# Configurable_RC_Filter.net
KiCad netlist of a schematic drawn in EAGLE
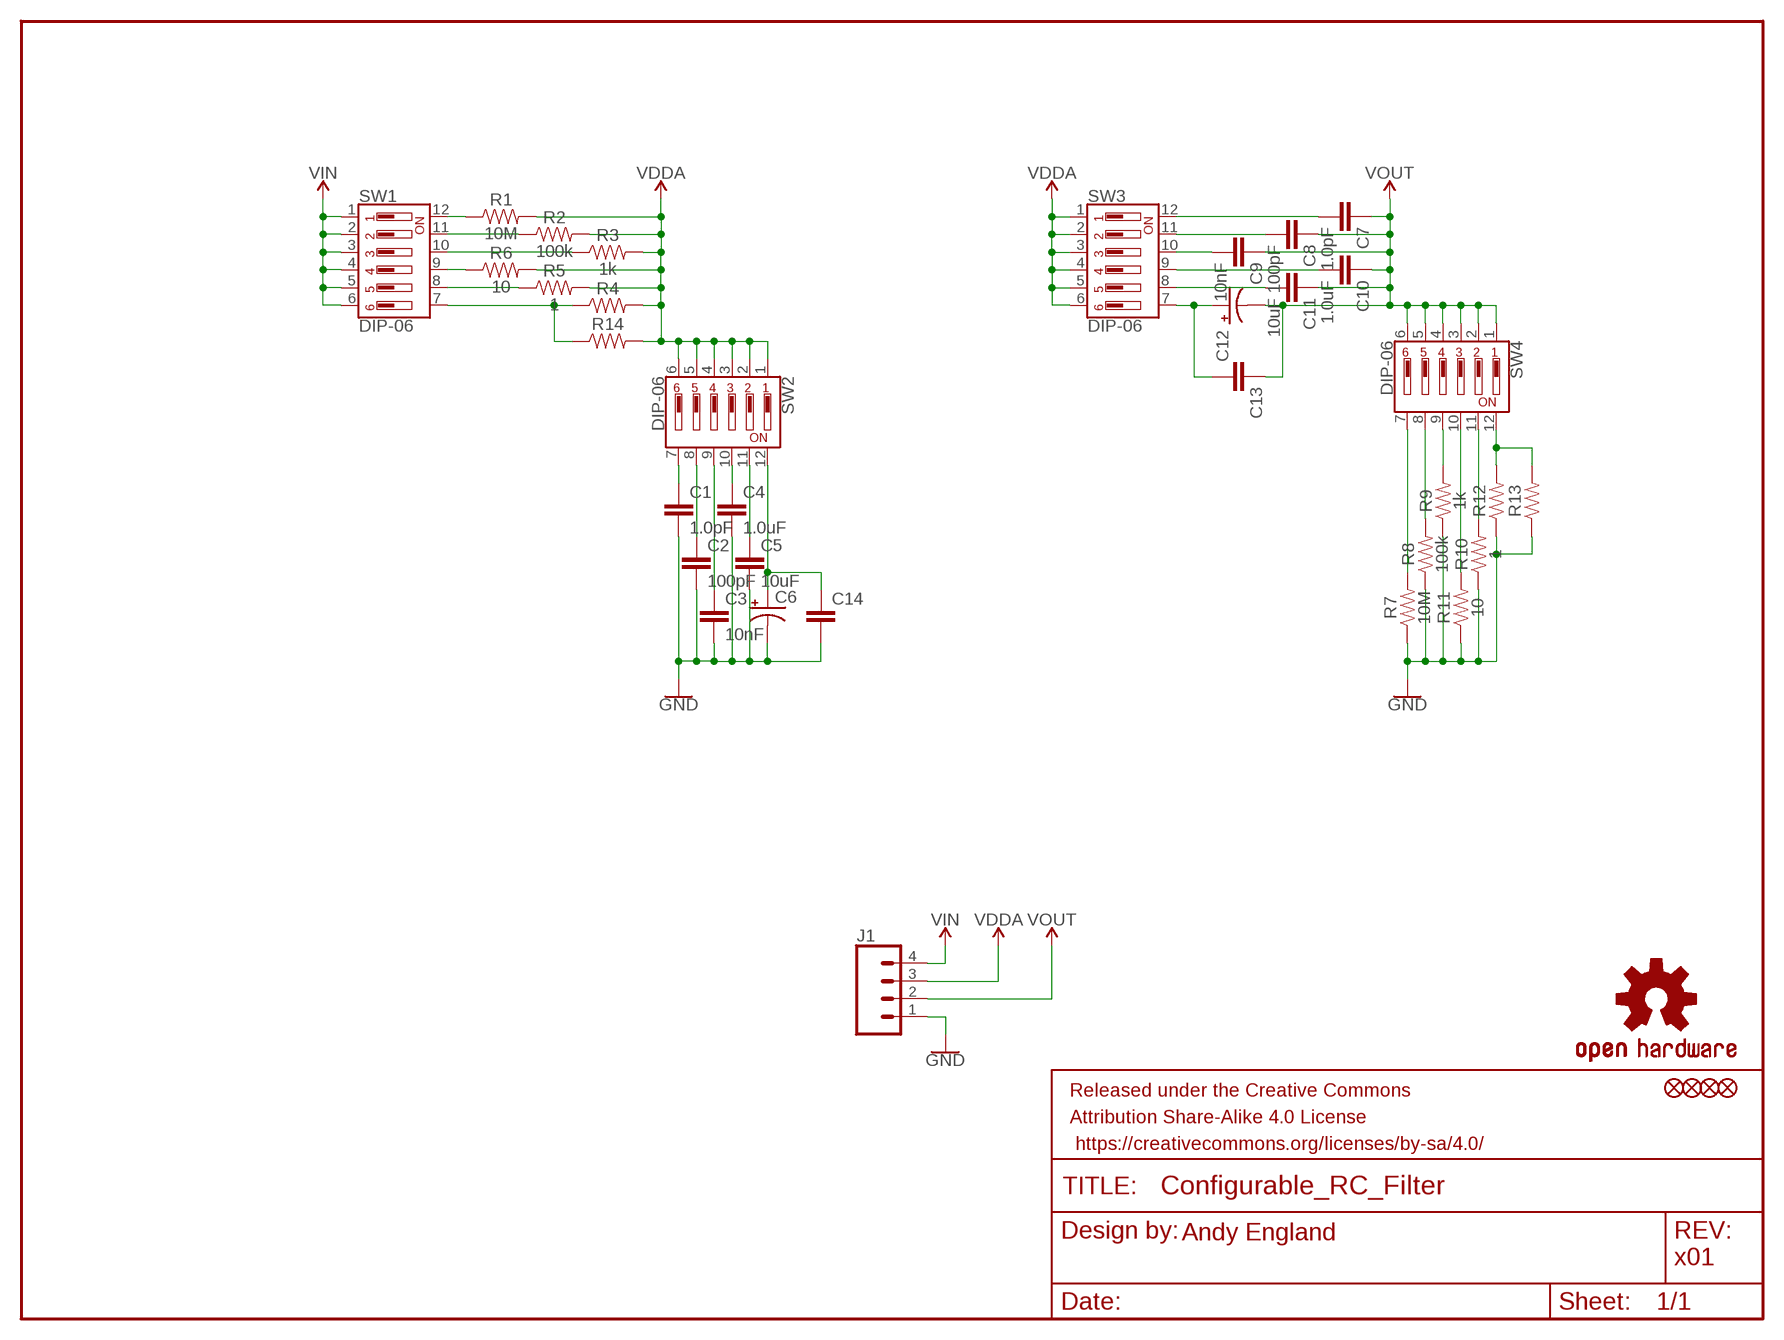
[diagram p0: schematic, sheet 1]

(export (version "E")
  (design (tool "Eeschema 10.0.6"))
  (components
    (comp (ref "C1")
      (value "1.0pF")
      (footprint "eagle-import:0603")
      (libsource (lib "eagle-import") (part "1.0PF-0603-50V-25%"))
    )
    (comp (ref "C2")
      (value "100pF")
      (footprint "eagle-import:0603")
      (libsource (lib "eagle-import") (part "100PF-0603-50V-5%"))
    )
    (comp (ref "C3")
      (value "10nF")
      (footprint "eagle-import:0603")
      (libsource (lib "eagle-import") (part "10NF-0603-50V-10%"))
    )
    (comp (ref "C4")
      (value "1.0uF")
      (footprint "eagle-import:0603")
      (libsource (lib "eagle-import") (part "1.0UF-0603-16V-10%"))
    )
    (comp (ref "C5")
      (value "10uF")
      (footprint "eagle-import:0603")
      (libsource (lib "eagle-import") (part "10UF-0603-6.3V-20%"))
    )
    (comp (ref "C6")
      (value "1000UF-RADIAL-5MM-25V-20%-NO-SILK")
      (footprint "eagle-import:CPOL-RADIAL-5MM-10MM-NS")
      (libsource (lib "eagle-import") (part "1000UF-RADIAL-5MM-25V-20%-NO-SILK"))
    )
    (comp (ref "C7")
      (value "1.0pF")
      (footprint "eagle-import:0603")
      (libsource (lib "eagle-import") (part "1.0PF-0603-50V-25%"))
    )
    (comp (ref "C8")
      (value "100pF")
      (footprint "eagle-import:0603")
      (libsource (lib "eagle-import") (part "100PF-0603-50V-5%"))
    )
    (comp (ref "C9")
      (value "10nF")
      (footprint "eagle-import:0603")
      (libsource (lib "eagle-import") (part "10NF-0603-50V-10%"))
    )
    (comp (ref "C10")
      (value "1.0uF")
      (footprint "eagle-import:0603")
      (libsource (lib "eagle-import") (part "1.0UF-0603-16V-10%"))
    )
    (comp (ref "C11")
      (value "10uF")
      (footprint "eagle-import:0603")
      (libsource (lib "eagle-import") (part "10UF-0603-6.3V-20%"))
    )
    (comp (ref "C12")
      (value "1000UF-RADIAL-5MM-25V-20%-NO-SILK")
      (footprint "eagle-import:CPOL-RADIAL-5MM-10MM-NS")
      (libsource (lib "eagle-import") (part "1000UF-RADIAL-5MM-25V-20%-NO-SILK"))
    )
    (comp (ref "C13")
      (value "CAP-0603")
      (footprint "eagle-import:0603")
      (libsource (lib "eagle-import") (part "CAP-0603"))
    )
    (comp (ref "C14")
      (value "CAP-0603")
      (footprint "eagle-import:0603")
      (libsource (lib "eagle-import") (part "CAP-0603"))
    )
    (comp (ref "FD1")
      (value "FIDUCIAL1X2")
      (footprint "eagle-import:FIDUCIAL-1X2")
      (libsource (lib "eagle-import") (part "FIDUCIAL1X2"))
    )
    (comp (ref "FD2")
      (value "FIDUCIAL1X2")
      (footprint "eagle-import:FIDUCIAL-1X2")
      (libsource (lib "eagle-import") (part "FIDUCIAL1X2"))
    )
    (comp (ref "FD3")
      (value "FIDUCIAL1X2")
      (footprint "eagle-import:FIDUCIAL-1X2")
      (libsource (lib "eagle-import") (part "FIDUCIAL1X2"))
    )
    (comp (ref "FD4")
      (value "FIDUCIAL1X2")
      (footprint "eagle-import:FIDUCIAL-1X2")
      (libsource (lib "eagle-import") (part "FIDUCIAL1X2"))
    )
    (comp (ref "FRAME1")
      (value "FRAME-LETTER")
      (footprint "eagle-import:CREATIVE_COMMONS")
      (libsource (lib "eagle-import") (part "FRAME-LETTER"))
    )
    (comp (ref "J1")
      (value "CONN_041X04_NO_SILK")
      (footprint "eagle-import:1X04_NO_SILK")
      (libsource (lib "eagle-import") (part "CONN_041X04_NO_SILK"))
    )
    (comp (ref "LOGO1")
      (value "OSHW-LOGOS")
      (footprint "eagle-import:OSHW-LOGO-S")
      (libsource (lib "eagle-import") (part "OSHW-LOGOS"))
    )
    (comp (ref "R1")
      (value "10M")
      (footprint "eagle-import:0603")
      (libsource (lib "eagle-import") (part "10MOHM-0603-1/10W-5%"))
    )
    (comp (ref "R2")
      (value "100k")
      (footprint "eagle-import:0603")
      (libsource (lib "eagle-import") (part "100KOHM-0603-1/10W-1%"))
    )
    (comp (ref "R3")
      (value "1k")
      (footprint "eagle-import:0603")
      (libsource (lib "eagle-import") (part "1KOHM-0603-1/10W-1%"))
    )
    (comp (ref "R4")
      (value "RESISTORAXIAL-0.3")
      (footprint "eagle-import:AXIAL-0.3")
      (libsource (lib "eagle-import") (part "RESISTORAXIAL-0.3"))
    )
    (comp (ref "R5")
      (value "1")
      (footprint "eagle-import:0603")
      (libsource (lib "eagle-import") (part "1OHM-0603-1/10W-1%"))
    )
    (comp (ref "R6")
      (value "10")
      (footprint "eagle-import:0603")
      (libsource (lib "eagle-import") (part "10OHM-0603-1/10W-1%"))
    )
    (comp (ref "R7")
      (value "10M")
      (footprint "eagle-import:0603")
      (libsource (lib "eagle-import") (part "10MOHM-0603-1/10W-5%"))
    )
    (comp (ref "R8")
      (value "100k")
      (footprint "eagle-import:0603")
      (libsource (lib "eagle-import") (part "100KOHM-0603-1/10W-1%"))
    )
    (comp (ref "R9")
      (value "1k")
      (footprint "eagle-import:0603")
      (libsource (lib "eagle-import") (part "1KOHM-0603-1/10W-1%"))
    )
    (comp (ref "R10")
      (value "1")
      (footprint "eagle-import:0603")
      (libsource (lib "eagle-import") (part "1OHM-0603-1/10W-1%"))
    )
    (comp (ref "R11")
      (value "10")
      (footprint "eagle-import:0603")
      (libsource (lib "eagle-import") (part "10OHM-0603-1/10W-1%"))
    )
    (comp (ref "R12")
      (value "RESISTORAXIAL-0.3")
      (footprint "eagle-import:AXIAL-0.3")
      (libsource (lib "eagle-import") (part "RESISTORAXIAL-0.3"))
    )
    (comp (ref "R13")
      (value "RESISTOR0603")
      (footprint "eagle-import:0603")
      (libsource (lib "eagle-import") (part "RESISTOR0603"))
    )
    (comp (ref "R14")
      (value "RESISTOR0603")
      (footprint "eagle-import:0603")
      (libsource (lib "eagle-import") (part "RESISTOR0603"))
    )
    (comp (ref "SW1")
      (value "DIP-06")
      (footprint "eagle-import:DIPSWITCH-06-SMD")
      (libsource (lib "eagle-import") (part "DIP-06"))
    )
    (comp (ref "SW2")
      (value "DIP-06")
      (footprint "eagle-import:DIPSWITCH-06-SMD")
      (libsource (lib "eagle-import") (part "DIP-06"))
    )
    (comp (ref "SW3")
      (value "DIP-06")
      (footprint "eagle-import:DIPSWITCH-06-SMD")
      (libsource (lib "eagle-import") (part "DIP-06"))
    )
    (comp (ref "SW4")
      (value "DIP-06")
      (footprint "eagle-import:DIPSWITCH-06-SMD")
      (libsource (lib "eagle-import") (part "DIP-06"))
    )
  )
  (nets
    (net (code "1") (name "GND") (class "Default")
      (node (ref "C1") (pin "2") (pinfunction "2_2") (pintype "passive"))
      (node (ref "C14") (pin "2") (pinfunction "2_2") (pintype "passive"))
      (node (ref "C2") (pin "2") (pinfunction "2_2") (pintype "passive"))
      (node (ref "C3") (pin "2") (pinfunction "2_2") (pintype "passive"))
      (node (ref "C4") (pin "2") (pinfunction "2_2") (pintype "passive"))
      (node (ref "C5") (pin "2") (pinfunction "2_2") (pintype "passive"))
      (node (ref "C6") (pin "-") (pinfunction "-_-") (pintype "passive"))
      (node (ref "J1") (pin "1") (pinfunction "1_1") (pintype "passive"))
      (node (ref "R10") (pin "1") (pinfunction "1_1") (pintype "passive"))
      (node (ref "R11") (pin "1") (pinfunction "1_1") (pintype "passive"))
      (node (ref "R12") (pin "P$1") (pinfunction "1_P$1") (pintype "passive"))
      (node (ref "R13") (pin "1") (pinfunction "1_1") (pintype "passive"))
      (node (ref "R7") (pin "1") (pinfunction "1_1") (pintype "passive"))
      (node (ref "R8") (pin "1") (pinfunction "1_1") (pintype "passive"))
      (node (ref "R9") (pin "1") (pinfunction "1_1") (pintype "passive"))
    )
    (net (code "2") (name "Net-(C1-Pad1)") (class "Default")
      (node (ref "C1") (pin "1") (pinfunction "1_1") (pintype "passive"))
      (node (ref "SW2") (pin "7") (pinfunction "7_7") (pintype "bidirectional"))
    )
    (net (code "3") (name "Net-(C2-Pad1)") (class "Default")
      (node (ref "C2") (pin "1") (pinfunction "1_1") (pintype "passive"))
      (node (ref "SW2") (pin "8") (pinfunction "8_8") (pintype "bidirectional"))
    )
    (net (code "4") (name "Net-(C3-Pad1)") (class "Default")
      (node (ref "C3") (pin "1") (pinfunction "1_1") (pintype "passive"))
      (node (ref "SW2") (pin "9") (pinfunction "9_9") (pintype "bidirectional"))
    )
    (net (code "5") (name "Net-(C4-Pad1)") (class "Default")
      (node (ref "C4") (pin "1") (pinfunction "1_1") (pintype "passive"))
      (node (ref "SW2") (pin "10") (pinfunction "10_10") (pintype "bidirectional"))
    )
    (net (code "6") (name "Net-(C5-Pad1)") (class "Default")
      (node (ref "C5") (pin "1") (pinfunction "1_1") (pintype "passive"))
      (node (ref "SW2") (pin "11") (pinfunction "11_11") (pintype "bidirectional"))
    )
    (net (code "7") (name "Net-(C7-Pad2)") (class "Default")
      (node (ref "C7") (pin "2") (pinfunction "2_2") (pintype "passive"))
      (node (ref "SW3") (pin "12") (pinfunction "12_12") (pintype "bidirectional"))
    )
    (net (code "8") (name "Net-(C8-Pad2)") (class "Default")
      (node (ref "C8") (pin "2") (pinfunction "2_2") (pintype "passive"))
      (node (ref "SW3") (pin "11") (pinfunction "11_11") (pintype "bidirectional"))
    )
    (net (code "9") (name "Net-(C9-Pad2)") (class "Default")
      (node (ref "C9") (pin "2") (pinfunction "2_2") (pintype "passive"))
      (node (ref "SW3") (pin "10") (pinfunction "10_10") (pintype "bidirectional"))
    )
    (net (code "10") (name "Net-(C10-Pad2)") (class "Default")
      (node (ref "C10") (pin "2") (pinfunction "2_2") (pintype "passive"))
      (node (ref "SW3") (pin "9") (pinfunction "9_9") (pintype "bidirectional"))
    )
    (net (code "11") (name "Net-(C11-Pad2)") (class "Default")
      (node (ref "C11") (pin "2") (pinfunction "2_2") (pintype "passive"))
      (node (ref "SW3") (pin "8") (pinfunction "8_8") (pintype "bidirectional"))
    )
    (net (code "12") (name "Net-(C12-Pad+)") (class "Default")
      (node (ref "C12") (pin "+") (pinfunction "+_+") (pintype "passive"))
      (node (ref "C13") (pin "2") (pinfunction "2_2") (pintype "passive"))
      (node (ref "SW3") (pin "7") (pinfunction "7_7") (pintype "bidirectional"))
    )
    (net (code "13") (name "Net-(C14-Pad1)") (class "Default")
      (node (ref "C14") (pin "1") (pinfunction "1_1") (pintype "passive"))
      (node (ref "C6") (pin "+") (pinfunction "+_+") (pintype "passive"))
      (node (ref "SW2") (pin "12") (pinfunction "12_12") (pintype "bidirectional"))
    )
    (net (code "14") (name "Net-(R1-Pad1)") (class "Default")
      (node (ref "R1") (pin "1") (pinfunction "1_1") (pintype "passive"))
      (node (ref "SW1") (pin "12") (pinfunction "12_12") (pintype "bidirectional"))
    )
    (net (code "15") (name "Net-(R2-Pad1)") (class "Default")
      (node (ref "R2") (pin "1") (pinfunction "1_1") (pintype "passive"))
      (node (ref "SW1") (pin "11") (pinfunction "11_11") (pintype "bidirectional"))
    )
    (net (code "16") (name "Net-(R3-Pad1)") (class "Default")
      (node (ref "R3") (pin "1") (pinfunction "1_1") (pintype "passive"))
      (node (ref "SW1") (pin "10") (pinfunction "10_10") (pintype "bidirectional"))
    )
    (net (code "17") (name "Net-(R4-1)") (class "Default")
      (node (ref "R14") (pin "1") (pinfunction "1_1") (pintype "passive"))
      (node (ref "R4") (pin "P$1") (pinfunction "1_P$1") (pintype "passive"))
      (node (ref "SW1") (pin "7") (pinfunction "7_7") (pintype "bidirectional"))
    )
    (net (code "18") (name "Net-(R5-Pad1)") (class "Default")
      (node (ref "R5") (pin "1") (pinfunction "1_1") (pintype "passive"))
      (node (ref "SW1") (pin "8") (pinfunction "8_8") (pintype "bidirectional"))
    )
    (net (code "19") (name "Net-(R6-Pad1)") (class "Default")
      (node (ref "R6") (pin "1") (pinfunction "1_1") (pintype "passive"))
      (node (ref "SW1") (pin "9") (pinfunction "9_9") (pintype "bidirectional"))
    )
    (net (code "20") (name "Net-(R7-Pad2)") (class "Default")
      (node (ref "R7") (pin "2") (pinfunction "2_2") (pintype "passive"))
      (node (ref "SW4") (pin "7") (pinfunction "7_7") (pintype "bidirectional"))
    )
    (net (code "21") (name "Net-(R8-Pad2)") (class "Default")
      (node (ref "R8") (pin "2") (pinfunction "2_2") (pintype "passive"))
      (node (ref "SW4") (pin "8") (pinfunction "8_8") (pintype "bidirectional"))
    )
    (net (code "22") (name "Net-(R9-Pad2)") (class "Default")
      (node (ref "R9") (pin "2") (pinfunction "2_2") (pintype "passive"))
      (node (ref "SW4") (pin "9") (pinfunction "9_9") (pintype "bidirectional"))
    )
    (net (code "23") (name "Net-(R10-Pad2)") (class "Default")
      (node (ref "R10") (pin "2") (pinfunction "2_2") (pintype "passive"))
      (node (ref "SW4") (pin "11") (pinfunction "11_11") (pintype "bidirectional"))
    )
    (net (code "24") (name "Net-(R11-Pad2)") (class "Default")
      (node (ref "R11") (pin "2") (pinfunction "2_2") (pintype "passive"))
      (node (ref "SW4") (pin "10") (pinfunction "10_10") (pintype "bidirectional"))
    )
    (net (code "25") (name "Net-(R12-2)") (class "Default")
      (node (ref "R12") (pin "P$2") (pinfunction "2_P$2") (pintype "passive"))
      (node (ref "R13") (pin "2") (pinfunction "2_2") (pintype "passive"))
      (node (ref "SW4") (pin "12") (pinfunction "12_12") (pintype "bidirectional"))
    )
    (net (code "26") (name "VDDA") (class "Default")
      (node (ref "J1") (pin "3") (pinfunction "3_3") (pintype "passive"))
      (node (ref "R1") (pin "2") (pinfunction "2_2") (pintype "passive"))
      (node (ref "R14") (pin "2") (pinfunction "2_2") (pintype "passive"))
      (node (ref "R2") (pin "2") (pinfunction "2_2") (pintype "passive"))
      (node (ref "R3") (pin "2") (pinfunction "2_2") (pintype "passive"))
      (node (ref "R4") (pin "P$2") (pinfunction "2_P$2") (pintype "passive"))
      (node (ref "R5") (pin "2") (pinfunction "2_2") (pintype "passive"))
      (node (ref "R6") (pin "2") (pinfunction "2_2") (pintype "passive"))
      (node (ref "SW2") (pin "1") (pinfunction "1_1") (pintype "bidirectional"))
      (node (ref "SW2") (pin "2") (pinfunction "2_2") (pintype "bidirectional"))
      (node (ref "SW2") (pin "3") (pinfunction "3_3") (pintype "bidirectional"))
      (node (ref "SW2") (pin "4") (pinfunction "4_4") (pintype "bidirectional"))
      (node (ref "SW2") (pin "5") (pinfunction "5_5") (pintype "bidirectional"))
      (node (ref "SW2") (pin "6") (pinfunction "6_6") (pintype "bidirectional"))
      (node (ref "SW3") (pin "1") (pinfunction "1_1") (pintype "bidirectional"))
      (node (ref "SW3") (pin "2") (pinfunction "2_2") (pintype "bidirectional"))
      (node (ref "SW3") (pin "3") (pinfunction "3_3") (pintype "bidirectional"))
      (node (ref "SW3") (pin "4") (pinfunction "4_4") (pintype "bidirectional"))
      (node (ref "SW3") (pin "5") (pinfunction "5_5") (pintype "bidirectional"))
      (node (ref "SW3") (pin "6") (pinfunction "6_6") (pintype "bidirectional"))
    )
    (net (code "27") (name "VIN") (class "Default")
      (node (ref "J1") (pin "4") (pinfunction "4_4") (pintype "passive"))
      (node (ref "SW1") (pin "1") (pinfunction "1_1") (pintype "bidirectional"))
      (node (ref "SW1") (pin "2") (pinfunction "2_2") (pintype "bidirectional"))
      (node (ref "SW1") (pin "3") (pinfunction "3_3") (pintype "bidirectional"))
      (node (ref "SW1") (pin "4") (pinfunction "4_4") (pintype "bidirectional"))
      (node (ref "SW1") (pin "5") (pinfunction "5_5") (pintype "bidirectional"))
      (node (ref "SW1") (pin "6") (pinfunction "6_6") (pintype "bidirectional"))
    )
    (net (code "28") (name "VOUT") (class "Default")
      (node (ref "C10") (pin "1") (pinfunction "1_1") (pintype "passive"))
      (node (ref "C11") (pin "1") (pinfunction "1_1") (pintype "passive"))
      (node (ref "C12") (pin "-") (pinfunction "-_-") (pintype "passive"))
      (node (ref "C13") (pin "1") (pinfunction "1_1") (pintype "passive"))
      (node (ref "C7") (pin "1") (pinfunction "1_1") (pintype "passive"))
      (node (ref "C8") (pin "1") (pinfunction "1_1") (pintype "passive"))
      (node (ref "C9") (pin "1") (pinfunction "1_1") (pintype "passive"))
      (node (ref "J1") (pin "2") (pinfunction "2_2") (pintype "passive"))
      (node (ref "SW4") (pin "1") (pinfunction "1_1") (pintype "bidirectional"))
      (node (ref "SW4") (pin "2") (pinfunction "2_2") (pintype "bidirectional"))
      (node (ref "SW4") (pin "3") (pinfunction "3_3") (pintype "bidirectional"))
      (node (ref "SW4") (pin "4") (pinfunction "4_4") (pintype "bidirectional"))
      (node (ref "SW4") (pin "5") (pinfunction "5_5") (pintype "bidirectional"))
      (node (ref "SW4") (pin "6") (pinfunction "6_6") (pintype "bidirectional"))
    )
  )
)
